# G-Cacher-Schematic_2026-07-06.net
KiCad netlist of a schematic drawn in Altium Designer
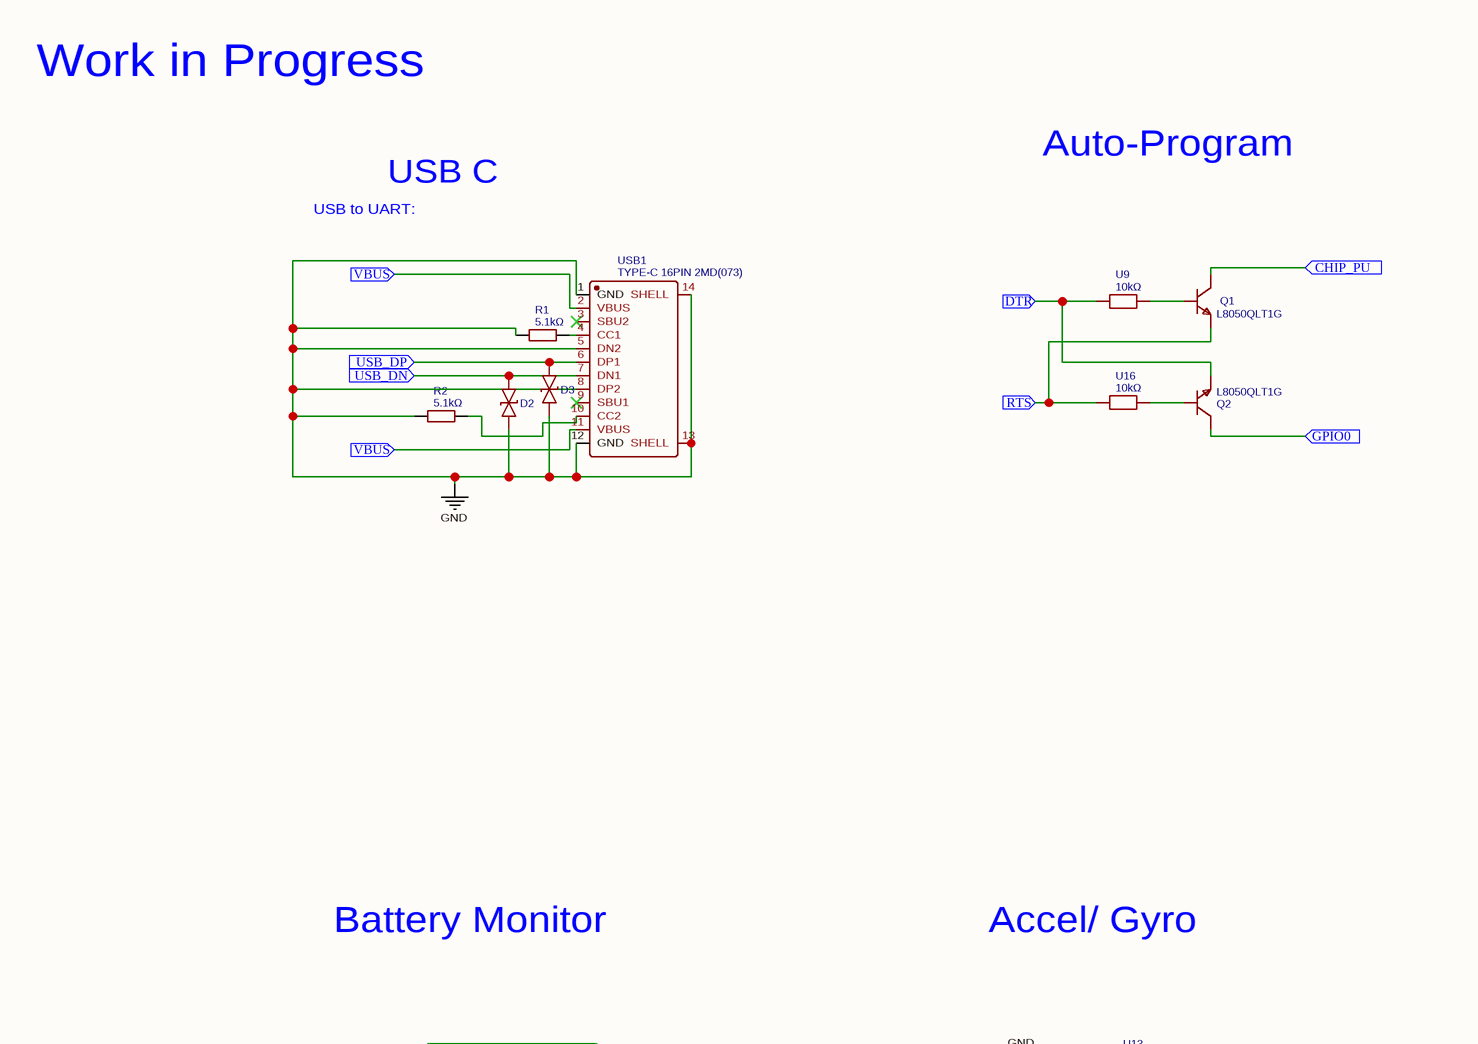
[diagram p0: G-Cacher-Schematic_2026-07-06.schdoc, top left]
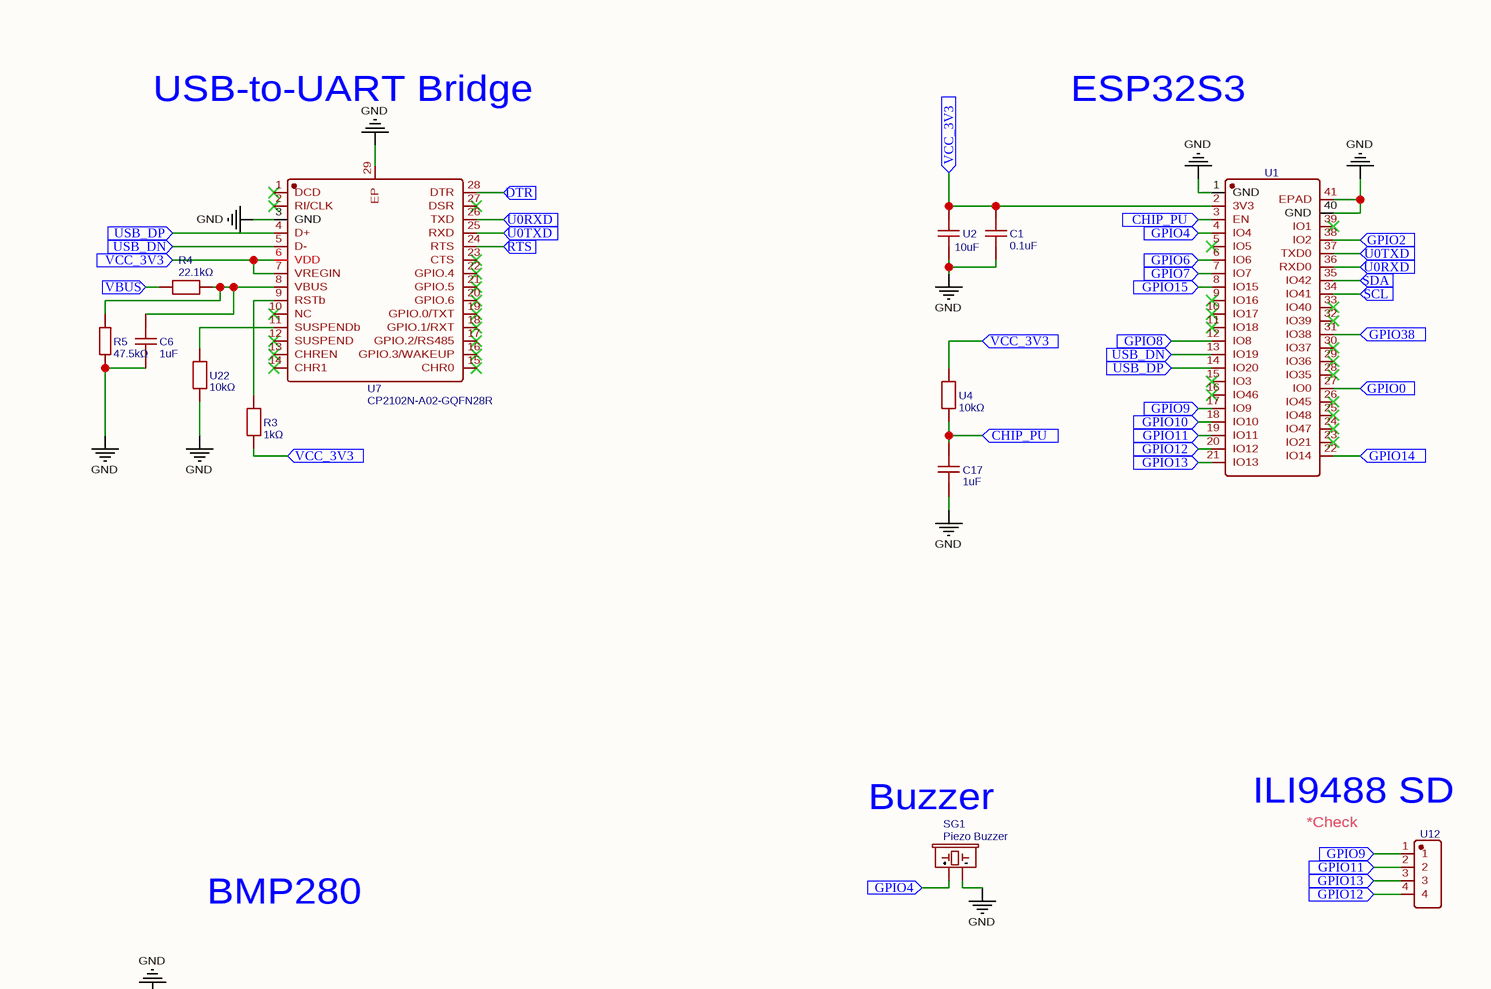
[diagram p1: G-Cacher-Schematic_2026-07-06.schdoc, top right]
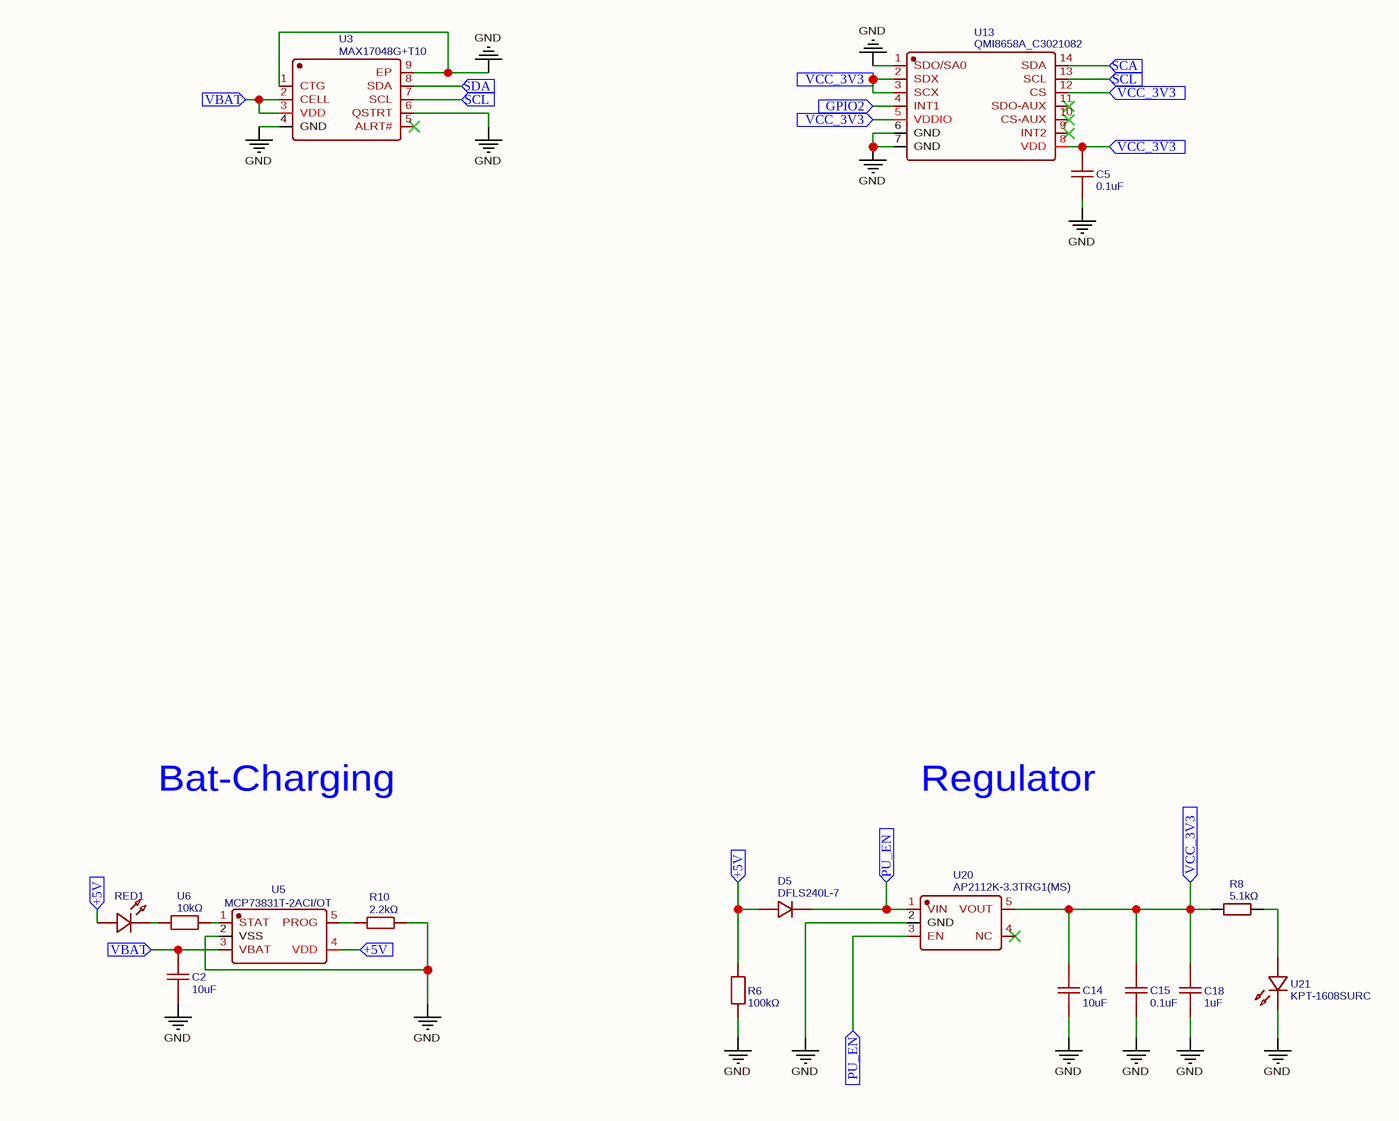
[diagram p2: G-Cacher-Schematic_2026-07-06.schdoc, bottom left]
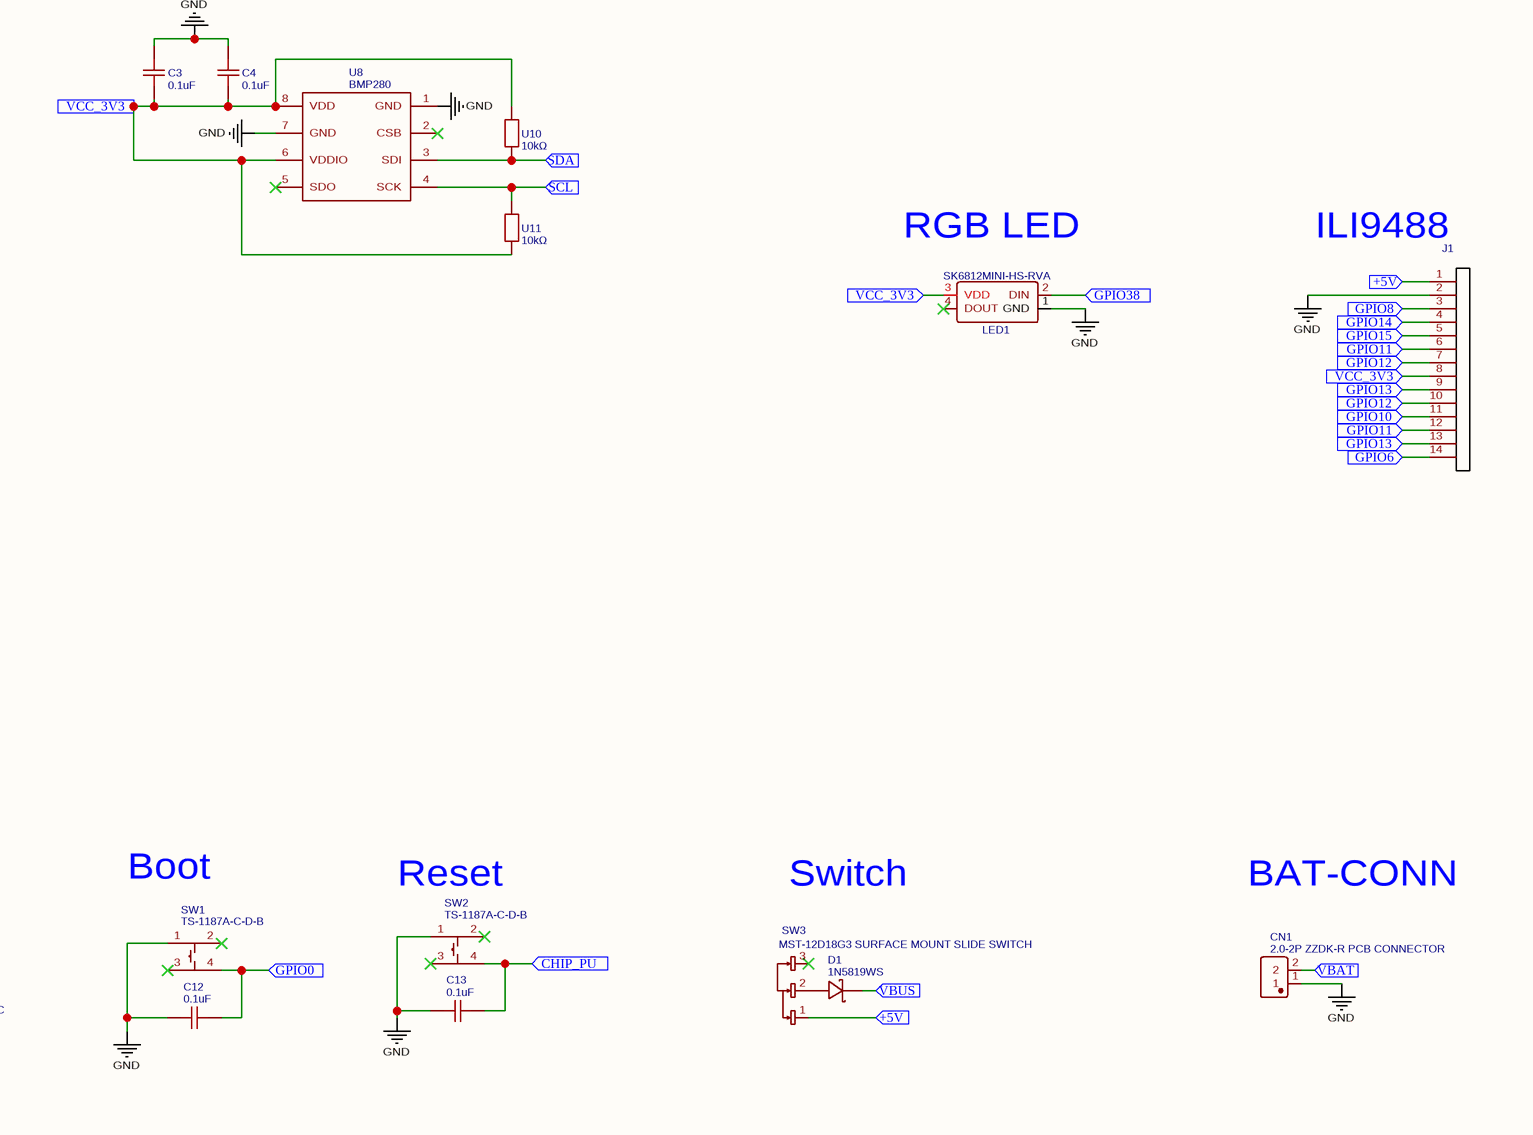
[diagram p3: G-Cacher-Schematic_2026-07-06.schdoc, bottom right]

(export (version "E")
  (design (tool "Eeschema 10.0.6"))
  (components
    (comp (ref "C1")
      (value "0.1uF")
      (fields
        (field (name "MANUFACTURER") "TDK")
        (field (name "MANUFACTURER PART") "C1005X5R1E104M050BC")
        (field (name "CONTRIBUTOR") "lcsc")
      )
      (libsource (lib "altium-import") (part "root_1_0.1uF_"))
    )
    (comp (ref "C2")
      (value "10uF")
      (fields (field (name "MANUFACTURER") "FH(风华)") (field (name "MANUFACTURER PART") "0603X106M100NT"))
      (libsource (lib "altium-import") (part "root_1_10uF_"))
    )
    (comp (ref "C3")
      (value "0.1uF")
      (fields
        (field (name "MANUFACTURER") "TDK")
        (field (name "MANUFACTURER PART") "C1005X5R1E104M050BC")
        (field (name "CONTRIBUTOR") "lcsc")
      )
      (libsource (lib "altium-import") (part "root_1_0.1uF_"))
    )
    (comp (ref "C4")
      (value "0.1uF")
      (fields
        (field (name "MANUFACTURER") "TDK")
        (field (name "MANUFACTURER PART") "C1005X5R1E104M050BC")
        (field (name "CONTRIBUTOR") "lcsc")
      )
      (libsource (lib "altium-import") (part "root_1_0.1uF_"))
    )
    (comp (ref "C5")
      (value "0.1uF")
      (fields
        (field (name "MANUFACTURER") "TDK")
        (field (name "MANUFACTURER PART") "C1005X5R1E104M050BC")
        (field (name "CONTRIBUTOR") "lcsc")
      )
      (libsource (lib "altium-import") (part "root_1_0.1uF_"))
    )
    (comp (ref "C6")
      (value "1uF")
      (fields
        (field (name "MANUFACTURER") "TDK")
        (field (name "MANUFACTURER PART") "YNA18B3U0G105MT000N")
        (field (name "CONTRIBUTOR") "lcsc")
      )
      (libsource (lib "altium-import") (part "root_1_1uF_"))
    )
    (comp (ref "C12")
      (value "0.1uF")
      (fields
        (field (name "MANUFACTURER") "TDK")
        (field (name "MANUFACTURER PART") "C1005X5R1E104M050BC")
        (field (name "CONTRIBUTOR") "lcsc")
      )
      (libsource (lib "altium-import") (part "root_2_0.1uF_"))
    )
    (comp (ref "C13")
      (value "0.1uF")
      (fields
        (field (name "MANUFACTURER") "TDK")
        (field (name "MANUFACTURER PART") "C1005X5R1E104M050BC")
        (field (name "CONTRIBUTOR") "lcsc")
      )
      (libsource (lib "altium-import") (part "root_2_0.1uF_"))
    )
    (comp (ref "C14")
      (value "10uF")
      (fields (field (name "MANUFACTURER") "FH(风华)") (field (name "MANUFACTURER PART") "0603X106M100NT"))
      (libsource (lib "altium-import") (part "root_1_10uF_"))
    )
    (comp (ref "C15")
      (value "0.1uF")
      (fields
        (field (name "MANUFACTURER") "TDK")
        (field (name "MANUFACTURER PART") "C1005X5R1E104M050BC")
        (field (name "CONTRIBUTOR") "lcsc")
      )
      (libsource (lib "altium-import") (part "root_1_0.1uF_"))
    )
    (comp (ref "C17")
      (value "1uF")
      (fields
        (field (name "MANUFACTURER") "TDK")
        (field (name "MANUFACTURER PART") "YNA18B3U0G105MT000N")
        (field (name "CONTRIBUTOR") "lcsc")
      )
      (libsource (lib "altium-import") (part "root_1_1uF_"))
    )
    (comp (ref "C18")
      (value "1uF")
      (fields
        (field (name "MANUFACTURER") "TDK")
        (field (name "MANUFACTURER PART") "YNA18B3U0G105MT000N")
        (field (name "CONTRIBUTOR") "lcsc")
      )
      (libsource (lib "altium-import") (part "root_1_1uF_"))
    )
    (comp (ref "CN1")
      (value "2.0-2P ZZDK-R PCB CONNECTOR")
      (fields
        (field (name "MANUFACTURER") "SHOU HAN(首韩)")
        (field (name "MANUFACTURER PART") "2.0-2P ZZDK-R PCB Connector")
        (field (name "CONTRIBUTOR") "lcsc")
      )
      (libsource (lib "altium-import") (part "root_2_2.0-2P ZZDK-R PCB CONNECTOR_"))
    )
    (comp (ref "D1")
      (value "1N5819WS")
      (fields (field (name "MANUFACTURER") "Hottech(合科泰)") (field (name "CONTRIBUTOR") "qarnet"))
      (libsource (lib "altium-import") (part "root_2_1N5819WS_"))
    )
    (comp (ref "D2")
      (value "LESD5D5.0CT1G")
      (fields (field (name "MANUFACTURER") "LRC(乐山无线电)") (field (name "CONTRIBUTOR") "LCSC"))
      (libsource (lib "altium-import") (part "root_3_LESD5D5.0CT1G_"))
    )
    (comp (ref "D3")
      (value "LESD5D5.0CT1G")
      (fields (field (name "MANUFACTURER") "LRC(乐山无线电)") (field (name "CONTRIBUTOR") "LCSC"))
      (libsource (lib "altium-import") (part "root_3_LESD5D5.0CT1G_"))
    )
    (comp (ref "D5")
      (value "DFLS240L-7")
      (fields (field (name "MANUFACTURER") "DIODES(美台)") (field (name "CONTRIBUTOR") "LCSC"))
      (libsource (lib "altium-import") (part "root_2_DFLS240L-7_"))
    )
    (comp (ref "J1")
      (value "14 PIN FEMALE HEADER")
      (fields (field (name "CONTRIBUTOR") "rnor"))
      (libsource (lib "altium-import") (part "root_0_14 PIN FEMALE HEADER_"))
    )
    (comp (ref "LED1")
      (value "SK6812MINI-HS-RVA")
      (fields (field (name "MANUFACTURER") "欧思科光电") (field (name "CONTRIBUTOR") "lcsc"))
      (libsource (lib "altium-import") (part "root_0_SK6812MINI-HS-RVA_"))
    )
    (comp (ref "Q1")
      (value "L8050QLT1G")
      (fields (field (name "MANUFACTURER") "LRC(乐山无线电)"))
      (libsource (lib "altium-import") (part "root_0_L8050QLT1G_"))
    )
    (comp (ref "Q2")
      (value "L8050QLT1G")
      (fields (field (name "MANUFACTURER") "LRC(乐山无线电)"))
      (libsource (lib "") (part "root_0_L8050QLT1G__1"))
    )
    (comp (ref "R1")
      (value "5.1kΩ")
      (fields
        (field (name "MANUFACTURER") "UNI-ROYAL(厚声)")
        (field (name "MANUFACTURER PART") "0402WGF5101TCE")
      )
      (libsource (lib "altium-import") (part "root_0_5.1kΩ_"))
    )
    (comp (ref "R2")
      (value "5.1kΩ")
      (fields
        (field (name "MANUFACTURER") "UNI-ROYAL(厚声)")
        (field (name "MANUFACTURER PART") "0402WGF5101TCE")
      )
      (libsource (lib "altium-import") (part "root_0_5.1kΩ_"))
    )
    (comp (ref "R3")
      (value "1kΩ")
      (fields
        (field (name "MANUFACTURER") "RESI(开步睿思)")
        (field (name "MANUFACTURER PART") "PTFR0603Q1K00N9")
        (field (name "CONTRIBUTOR") "lcsc")
      )
      (libsource (lib "altium-import") (part "root_1_1kΩ_"))
    )
    (comp (ref "R4")
      (value "22.1kΩ")
      (fields
        (field (name "MANUFACTURER") "FOJAN(富捷)")
        (field (name "MANUFACTURER PART") "FRC0402F2212TS")
        (field (name "CONTRIBUTOR") "lcsc")
      )
      (libsource (lib "altium-import") (part "root_0_22.1kΩ_"))
    )
    (comp (ref "R5")
      (value "47.5kΩ")
      (fields
        (field (name "MANUFACTURER") "FH(风华)")
        (field (name "MANUFACTURER PART") "RC-02K4752FT")
        (field (name "CONTRIBUTOR") "LCSC")
      )
      (libsource (lib "altium-import") (part "root_1_47.5kΩ_"))
    )
    (comp (ref "R6")
      (value "100kΩ")
      (fields
        (field (name "MANUFACTURER") "EVER OHMS(天二科技)")
        (field (name "MANUFACTURER PART") "TR0603B100KP0525Z")
        (field (name "CONTRIBUTOR") "lcsc")
      )
      (libsource (lib "altium-import") (part "root_1_100kΩ_"))
    )
    (comp (ref "R8")
      (value "5.1kΩ")
      (fields
        (field (name "MANUFACTURER") "UNI-ROYAL(厚声)")
        (field (name "MANUFACTURER PART") "0402WGF5101TCE")
      )
      (libsource (lib "altium-import") (part "root_0_5.1kΩ_"))
    )
    (comp (ref "R10")
      (value "2.2kΩ")
      (fields
        (field (name "MANUFACTURER") "Tyohm(幸亚电阻)")
        (field (name "MANUFACTURER PART") "RMC04022.2K5%N")
        (field (name "CONTRIBUTOR") "LCSC")
      )
      (libsource (lib "altium-import") (part "root_2_2.2kΩ_"))
    )
    (comp (ref "RED1")
      (value "F.0603.00008/P2-0603R1TS2-06T-002")
      (fields (field (name "MANUFACTURER") "TUOZHAN(拓展光电)") (field (name "CONTRIBUTOR") "lcsc"))
      (libsource (lib "altium-import") (part "root_0_F.0603.00008/P2-0603R1TS2-06T-002_"))
    )
    (comp (ref "SG1")
      (value "Piezo Buzzer")
      (fields (field (name "CONTRIBUTOR") "SparkFun"))
      (libsource (lib "altium-import") (part "root_0_Piezo Buzzer_"))
    )
    (comp (ref "SW1")
      (value "TS-1187A-C-D-B")
      (fields (field (name "MANUFACTURER") "XKB Connection(中国星坤)") (field (name "CONTRIBUTOR") "LCSC"))
      (libsource (lib "altium-import") (part "root_0_TS-1187A-C-D-B_"))
    )
    (comp (ref "SW2")
      (value "TS-1187A-C-D-B")
      (fields (field (name "MANUFACTURER") "XKB Connection(中国星坤)") (field (name "CONTRIBUTOR") "LCSC"))
      (libsource (lib "altium-import") (part "root_0_TS-1187A-C-D-B_"))
    )
    (comp (ref "SW3")
      (value "MST-12D18G3 SURFACE MOUNT SLIDE SWITCH")
      (fields
        (field (name "MANUFACTURER") "SHOU HAN(首韩)")
        (field (name "MANUFACTURER PART") "MST-12D18G3 Surface Mount Slide Switch")
        (field (name "CONTRIBUTOR") "lcsc")
      )
      (libsource (lib "altium-import") (part "root_1_MST-12D18G3 SURFACE MOUNT SLIDE SWITCH_"))
    )
    (comp (ref "U1")
      (value "ESPS3-32-WROOM-1-N16R8")
      (fields (field (name "CONTRIBUTOR") "lcsc"))
      (libsource (lib "altium-import") (part "root_0_ESPS3-32-WROOM-1-N16R8_"))
    )
    (comp (ref "U2")
      (value "10uF")
      (fields
        (field (name "MANUFACTURER") "Chinocera(华瓷)")
        (field (name "MANUFACTURER PART") "HGC0603R5106K250NTHJ")
        (field (name "CONTRIBUTOR") "lcsc")
      )
      (libsource (lib "altium-import") (part "root_1_10uF_"))
    )
    (comp (ref "U3")
      (value "MAX17048G+T10")
      (fields (field (name "MANUFACTURER") "ADI(亚德诺)/MAXIM(美信)") (field (name "CONTRIBUTOR") "LCSC"))
      (libsource (lib "altium-import") (part "root_0_MAX17048G+T10_"))
    )
    (comp (ref "U4")
      (value "10kΩ")
      (fields
        (field (name "MANUFACTURER") "FH(风华)")
        (field (name "MANUFACTURER PART") "THC02H1002BT")
        (field (name "CONTRIBUTOR") "lcsc")
      )
      (libsource (lib "altium-import") (part "root_1_10kΩ_"))
    )
    (comp (ref "U5")
      (value "MCP73831T-2ACI/OT")
      (fields (field (name "MANUFACTURER") "MICROCHIP(美国微芯)") (field (name "CONTRIBUTOR") "LCSC"))
      (libsource (lib "altium-import") (part "root_0_MCP73831T-2ACI/OT_"))
    )
    (comp (ref "U6")
      (value "10kΩ")
      (fields
        (field (name "MANUFACTURER") "TE Connectivity(泰科电子)")
        (field (name "MANUFACTURER PART") "CRGH0603F10K")
        (field (name "CONTRIBUTOR") "lcsc")
      )
      (libsource (lib "altium-import") (part "root_2_10kΩ_"))
    )
    (comp (ref "U7")
      (value "CP2102N-A02-GQFN28R")
      (fields (field (name "MANUFACTURER") "SKYWORKS/SILICON LABS(芯科)") (field (name "CONTRIBUTOR") "LCSC"))
      (libsource (lib "altium-import") (part "root_0_CP2102N-A02-GQFN28R_"))
    )
    (comp (ref "U8")
      (value "BMP280")
      (fields (field (name "MANUFACTURER") "Bosch(博世)"))
      (libsource (lib "altium-import") (part "root_0_BMP280_"))
    )
    (comp (ref "U9")
      (value "10kΩ")
      (fields
        (field (name "MANUFACTURER") "TE Connectivity(泰科电子)")
        (field (name "MANUFACTURER PART") "CRGH0603F10K")
        (field (name "CONTRIBUTOR") "lcsc")
      )
      (libsource (lib "altium-import") (part "root_0_10kΩ_"))
    )
    (comp (ref "U10")
      (value "10kΩ")
      (fields
        (field (name "MANUFACTURER") "TE Connectivity(泰科电子)")
        (field (name "MANUFACTURER PART") "CRGH0603F10K")
        (field (name "CONTRIBUTOR") "lcsc")
      )
      (libsource (lib "altium-import") (part "root_3_10kΩ_"))
    )
    (comp (ref "U11")
      (value "10kΩ")
      (fields
        (field (name "MANUFACTURER") "TE Connectivity(泰科电子)")
        (field (name "MANUFACTURER PART") "CRGH0603F10K")
        (field (name "CONTRIBUTOR") "lcsc")
      )
      (libsource (lib "altium-import") (part "root_1_10kΩ_"))
    )
    (comp (ref "U12")
      (value "SSW-104-01-T-S")
      (fields (field (name "MANUFACTURER") "SAMTEC") (field (name "CONTRIBUTOR") "lcsc"))
      (libsource (lib "altium-import") (part "root_0_SSW-104-01-T-S_"))
    )
    (comp (ref "U13")
      (value "QMI8658A_C3021082")
      (fields
        (field (name "MANUFACTURER") "QST(上海矽睿)")
        (field (name "MANUFACTURER PART") "QMI8658A")
        (field (name "CONTRIBUTOR") "lcsc")
      )
      (libsource (lib "altium-import") (part "root_0_QMI8658A_C3021082_"))
    )
    (comp (ref "U16")
      (value "10kΩ")
      (fields
        (field (name "MANUFACTURER") "TE Connectivity(泰科电子)")
        (field (name "MANUFACTURER PART") "CRGH0603F10K")
        (field (name "CONTRIBUTOR") "lcsc")
      )
      (libsource (lib "altium-import") (part "root_0_10kΩ_"))
    )
    (comp (ref "U20")
      (value "AP2112K-3.3TRG1(MS)")
      (fields (field (name "MANUFACTURER") "MSKSEMI(美森科)") (field (name "CONTRIBUTOR") "lcsc"))
      (libsource (lib "altium-import") (part "root_0_AP2112K-3.3TRG1(MS)_"))
    )
    (comp (ref "U21")
      (value "KPT-1608SURC")
      (fields (field (name "MANUFACTURER") "Kingbright") (field (name "CONTRIBUTOR") "lcsc"))
      (libsource (lib "altium-import") (part "root_1_KPT-1608SURC_"))
    )
    (comp (ref "U22")
      (value "10kΩ")
      (fields
        (field (name "MANUFACTURER") "TE Connectivity(泰科电子)")
        (field (name "MANUFACTURER PART") "CRGH0603F10K")
        (field (name "CONTRIBUTOR") "lcsc")
      )
      (libsource (lib "altium-import") (part "root_1_10kΩ_"))
    )
    (comp (ref "USB1")
      (value "TYPE-C 16PIN 2MD(073)")
      (fields (field (name "MANUFACTURER") "SHOU HAN(首韩)") (field (name "CONTRIBUTOR") "LCSC"))
      (libsource (lib "altium-import") (part "root_0_TYPE-C 16PIN 2MD(073)_"))
    )
  )
  (nets
    (net (code "1") (name "/+5V") (class "Default")
      (node (ref "D5") (pin "2") (pinfunction "2_2") (pintype "passive"))
      (node (ref "J1") (pin "1") (pinfunction "1_1") (pintype "passive"))
      (node (ref "R6") (pin "2") (pinfunction "2_2") (pintype "passive"))
      (node (ref "RED1") (pin "1") (pinfunction "+_1") (pintype "passive"))
      (node (ref "SW3") (pin "1") (pinfunction "1_1") (pintype "passive"))
      (node (ref "U5") (pin "4") (pinfunction "VDD_4") (pintype "passive"))
    )
    (net (code "2") (name "/CHIP_PU") (class "Default")
      (node (ref "C13") (pin "1") (pinfunction "1_1") (pintype "passive"))
      (node (ref "C17") (pin "2") (pinfunction "2_2") (pintype "passive"))
      (node (ref "Q1") (pin "3") (pinfunction "C_3") (pintype "passive"))
      (node (ref "SW2") (pin "4") (pinfunction "D_4") (pintype "passive"))
      (node (ref "U1") (pin "3") (pinfunction "EN_3") (pintype "passive"))
      (node (ref "U4") (pin "1") (pinfunction "1_1") (pintype "passive"))
    )
    (net (code "3") (name "/DTR") (class "Default")
      (node (ref "Q2") (pin "2") (pinfunction "E_2") (pintype "passive"))
      (node (ref "U7") (pin "28") (pinfunction "DTR_28") (pintype "passive"))
      (node (ref "U9") (pin "1") (pinfunction "1_1") (pintype "passive"))
    )
    (net (code "4") (name "/GPIO0") (class "Default")
      (node (ref "C12") (pin "1") (pinfunction "1_1") (pintype "passive"))
      (node (ref "Q2") (pin "3") (pinfunction "C_3") (pintype "passive"))
      (node (ref "SW1") (pin "4") (pinfunction "D_4") (pintype "passive"))
      (node (ref "U1") (pin "27") (pinfunction "IO0_27") (pintype "passive"))
    )
    (net (code "5") (name "/GPIO2") (class "Default")
      (node (ref "U1") (pin "38") (pinfunction "IO2_38") (pintype "passive"))
      (node (ref "U13") (pin "4") (pinfunction "INT1_4") (pintype "passive"))
    )
    (net (code "6") (name "/GPIO4") (class "Default")
      (node (ref "SG1") (pin "+") (pinfunction "1_+") (pintype "passive"))
      (node (ref "U1") (pin "4") (pinfunction "IO4_4") (pintype "passive"))
    )
    (net (code "7") (name "/GPIO6") (class "Default")
      (node (ref "J1") (pin "14") (pinfunction "14_14") (pintype "passive"))
      (node (ref "U1") (pin "6") (pinfunction "IO6_6") (pintype "passive"))
    )
    (net (code "8") (name "/GPIO7") (class "Default")
      (node (ref "U1") (pin "7") (pinfunction "IO7_7") (pintype "passive"))
    )
    (net (code "9") (name "/GPIO8") (class "Default")
      (node (ref "J1") (pin "3") (pinfunction "3_3") (pintype "passive"))
      (node (ref "U1") (pin "12") (pinfunction "IO8_12") (pintype "passive"))
    )
    (net (code "10") (name "/GPIO9") (class "Default")
      (node (ref "U1") (pin "17") (pinfunction "IO9_17") (pintype "passive"))
      (node (ref "U12") (pin "1") (pinfunction "1_1") (pintype "passive"))
    )
    (net (code "11") (name "/GPIO10") (class "Default")
      (node (ref "J1") (pin "11") (pinfunction "11_11") (pintype "passive"))
      (node (ref "U1") (pin "18") (pinfunction "IO10_18") (pintype "passive"))
    )
    (net (code "12") (name "/GPIO11") (class "Default")
      (node (ref "J1") (pin "12") (pinfunction "12_12") (pintype "passive"))
      (node (ref "J1") (pin "6") (pinfunction "6_6") (pintype "passive"))
      (node (ref "U1") (pin "19") (pinfunction "IO11_19") (pintype "passive"))
      (node (ref "U12") (pin "2") (pinfunction "2_2") (pintype "passive"))
    )
    (net (code "13") (name "/GPIO12") (class "Default")
      (node (ref "J1") (pin "10") (pinfunction "10_10") (pintype "passive"))
      (node (ref "J1") (pin "7") (pinfunction "7_7") (pintype "passive"))
      (node (ref "U1") (pin "20") (pinfunction "IO12_20") (pintype "passive"))
      (node (ref "U12") (pin "4") (pinfunction "4_4") (pintype "passive"))
    )
    (net (code "14") (name "/GPIO13") (class "Default")
      (node (ref "J1") (pin "13") (pinfunction "13_13") (pintype "passive"))
      (node (ref "J1") (pin "9") (pinfunction "9_9") (pintype "passive"))
      (node (ref "U1") (pin "21") (pinfunction "IO13_21") (pintype "passive"))
      (node (ref "U12") (pin "3") (pinfunction "3_3") (pintype "passive"))
    )
    (net (code "15") (name "/GPIO14") (class "Default")
      (node (ref "J1") (pin "4") (pinfunction "4_4") (pintype "passive"))
      (node (ref "U1") (pin "22") (pinfunction "IO14_22") (pintype "passive"))
    )
    (net (code "16") (name "/GPIO15") (class "Default")
      (node (ref "J1") (pin "5") (pinfunction "5_5") (pintype "passive"))
      (node (ref "U1") (pin "8") (pinfunction "IO15_8") (pintype "passive"))
    )
    (net (code "17") (name "/GPIO38") (class "Default")
      (node (ref "LED1") (pin "2") (pinfunction "DIN_2") (pintype "passive"))
      (node (ref "U1") (pin "31") (pinfunction "IO38_31") (pintype "passive"))
    )
    (net (code "18") (name "/PU_EN") (class "Default")
      (node (ref "D5") (pin "1") (pinfunction "1_1") (pintype "passive"))
      (node (ref "U20") (pin "1") (pinfunction "VIN_1") (pintype "passive"))
      (node (ref "U20") (pin "3") (pinfunction "EN_3") (pintype "passive"))
    )
    (net (code "19") (name "/RTS") (class "Default")
      (node (ref "Q1") (pin "2") (pinfunction "E_2") (pintype "passive"))
      (node (ref "U16") (pin "1") (pinfunction "1_1") (pintype "passive"))
      (node (ref "U7") (pin "24") (pinfunction "RTS_24") (pintype "passive"))
    )
    (net (code "20") (name "/SCA") (class "Default")
      (node (ref "U13") (pin "14") (pinfunction "SDA_14") (pintype "passive"))
    )
    (net (code "21") (name "/SCL") (class "Default")
      (node (ref "U1") (pin "34") (pinfunction "IO41_34") (pintype "passive"))
      (node (ref "U11") (pin "2") (pinfunction "2_2") (pintype "passive"))
      (node (ref "U13") (pin "13") (pinfunction "SCL_13") (pintype "passive"))
      (node (ref "U3") (pin "7") (pinfunction "SCL_7") (pintype "passive"))
      (node (ref "U8") (pin "4") (pinfunction "SCK_4") (pintype "passive"))
    )
    (net (code "22") (name "/SDA") (class "Default")
      (node (ref "U1") (pin "35") (pinfunction "IO42_35") (pintype "passive"))
      (node (ref "U10") (pin "2") (pinfunction "2_2") (pintype "passive"))
      (node (ref "U3") (pin "8") (pinfunction "SDA_8") (pintype "passive"))
      (node (ref "U8") (pin "3") (pinfunction "SDI_3") (pintype "passive"))
    )
    (net (code "23") (name "/U0RXD") (class "Default")
      (node (ref "U1") (pin "36") (pinfunction "RXD0_36") (pintype "passive"))
      (node (ref "U7") (pin "26") (pinfunction "TXD_26") (pintype "passive"))
    )
    (net (code "24") (name "/U0TXD") (class "Default")
      (node (ref "U1") (pin "37") (pinfunction "TXD0_37") (pintype "passive"))
      (node (ref "U7") (pin "25") (pinfunction "RXD_25") (pintype "passive"))
    )
    (net (code "25") (name "/USB_DN") (class "Default")
      (node (ref "D2") (pin "1") (pinfunction "1_1") (pintype "passive"))
      (node (ref "U1") (pin "13") (pinfunction "IO19_13") (pintype "passive"))
      (node (ref "U7") (pin "5") (pinfunction "D-_5") (pintype "passive"))
      (node (ref "USB1") (pin "7") (pinfunction "DN1_7") (pintype "passive"))
    )
    (net (code "26") (name "/USB_DP") (class "Default")
      (node (ref "D3") (pin "1") (pinfunction "1_1") (pintype "passive"))
      (node (ref "U1") (pin "14") (pinfunction "IO20_14") (pintype "passive"))
      (node (ref "U7") (pin "4") (pinfunction "D+_4") (pintype "passive"))
      (node (ref "USB1") (pin "6") (pinfunction "DP1_6") (pintype "passive"))
    )
    (net (code "27") (name "/VBAT") (class "Default")
      (node (ref "C2") (pin "2") (pinfunction "2_2") (pintype "passive"))
      (node (ref "CN1") (pin "2") (pinfunction "2_2") (pintype "passive"))
      (node (ref "U3") (pin "2") (pinfunction "CELL_2") (pintype "passive"))
      (node (ref "U3") (pin "3") (pinfunction "VDD_3") (pintype "passive"))
      (node (ref "U5") (pin "3") (pinfunction "VBAT_3") (pintype "passive"))
    )
    (net (code "28") (name "/VBUS") (class "Default")
      (node (ref "D1") (pin "1") (pinfunction "K_1") (pintype "passive"))
      (node (ref "R4") (pin "1") (pinfunction "1_1") (pintype "passive"))
      (node (ref "USB1") (pin "11") (pinfunction "VBUS_11") (pintype "passive"))
      (node (ref "USB1") (pin "2") (pinfunction "VBUS_2") (pintype "passive"))
    )
    (net (code "29") (name "/VCC_3V3") (class "Default")
      (node (ref "C1") (pin "2") (pinfunction "2_2") (pintype "passive"))
      (node (ref "C14") (pin "2") (pinfunction "2_2") (pintype "passive"))
      (node (ref "C15") (pin "2") (pinfunction "2_2") (pintype "passive"))
      (node (ref "C18") (pin "2") (pinfunction "2_2") (pintype "passive"))
      (node (ref "C3") (pin "1") (pinfunction "1_1") (pintype "passive"))
      (node (ref "C4") (pin "1") (pinfunction "1_1") (pintype "passive"))
      (node (ref "C5") (pin "2") (pinfunction "2_2") (pintype "passive"))
      (node (ref "J1") (pin "8") (pinfunction "8_8") (pintype "passive"))
      (node (ref "LED1") (pin "3") (pinfunction "VDD_3") (pintype "passive"))
      (node (ref "R3") (pin "1") (pinfunction "1_1") (pintype "passive"))
      (node (ref "R8") (pin "1") (pinfunction "1_1") (pintype "passive"))
      (node (ref "U1") (pin "2") (pinfunction "3V3_2") (pintype "passive"))
      (node (ref "U10") (pin "1") (pinfunction "1_1") (pintype "passive"))
      (node (ref "U11") (pin "1") (pinfunction "1_1") (pintype "passive"))
      (node (ref "U13") (pin "12") (pinfunction "CS_12") (pintype "passive"))
      (node (ref "U13") (pin "2") (pinfunction "SDX_2") (pintype "passive"))
      (node (ref "U13") (pin "3") (pinfunction "SCX_3") (pintype "passive"))
      (node (ref "U13") (pin "5") (pinfunction "VDDIO_5") (pintype "passive"))
      (node (ref "U13") (pin "8") (pinfunction "VDD_8") (pintype "passive"))
      (node (ref "U2") (pin "2") (pinfunction "2_2") (pintype "passive"))
      (node (ref "U20") (pin "5") (pinfunction "VOUT_5") (pintype "passive"))
      (node (ref "U4") (pin "2") (pinfunction "2_2") (pintype "passive"))
      (node (ref "U7") (pin "6") (pinfunction "VDD_6") (pintype "passive"))
      (node (ref "U7") (pin "7") (pinfunction "VREGIN_7") (pintype "passive"))
      (node (ref "U8") (pin "6") (pinfunction "VDDIO_6") (pintype "passive"))
      (node (ref "U8") (pin "8") (pinfunction "VDD_8") (pintype "passive"))
    )
    (net (code "30") (name "GND") (class "Default")
      (node (ref "C1") (pin "1") (pinfunction "1_1") (pintype "passive"))
      (node (ref "C12") (pin "2") (pinfunction "2_2") (pintype "passive"))
      (node (ref "C13") (pin "2") (pinfunction "2_2") (pintype "passive"))
      (node (ref "C14") (pin "1") (pinfunction "1_1") (pintype "passive"))
      (node (ref "C15") (pin "1") (pinfunction "1_1") (pintype "passive"))
      (node (ref "C17") (pin "1") (pinfunction "1_1") (pintype "passive"))
      (node (ref "C18") (pin "1") (pinfunction "1_1") (pintype "passive"))
      (node (ref "C2") (pin "1") (pinfunction "1_1") (pintype "passive"))
      (node (ref "C3") (pin "2") (pinfunction "2_2") (pintype "passive"))
      (node (ref "C4") (pin "2") (pinfunction "2_2") (pintype "passive"))
      (node (ref "C5") (pin "1") (pinfunction "1_1") (pintype "passive"))
      (node (ref "C6") (pin "1") (pinfunction "1_1") (pintype "passive"))
      (node (ref "CN1") (pin "1") (pinfunction "1_1") (pintype "passive"))
      (node (ref "D2") (pin "2") (pinfunction "2_2") (pintype "passive"))
      (node (ref "D3") (pin "2") (pinfunction "2_2") (pintype "passive"))
      (node (ref "J1") (pin "2") (pinfunction "2_2") (pintype "passive"))
      (node (ref "LED1") (pin "1") (pinfunction "GND_1") (pintype "passive"))
      (node (ref "R1") (pin "1") (pinfunction "1_1") (pintype "passive"))
      (node (ref "R10") (pin "1") (pinfunction "1_1") (pintype "passive"))
      (node (ref "R2") (pin "1") (pinfunction "1_1") (pintype "passive"))
      (node (ref "R5") (pin "1") (pinfunction "1_1") (pintype "passive"))
      (node (ref "R6") (pin "1") (pinfunction "1_1") (pintype "passive"))
      (node (ref "SG1") (pin "-") (pinfunction "2_-") (pintype "passive"))
      (node (ref "SW1") (pin "1") (pinfunction "A_1") (pintype "passive"))
      (node (ref "SW2") (pin "1") (pinfunction "A_1") (pintype "passive"))
      (node (ref "U1") (pin "1") (pinfunction "GND_1") (pintype "passive"))
      (node (ref "U1") (pin "40") (pinfunction "GND_40") (pintype "passive"))
      (node (ref "U1") (pin "41") (pinfunction "EPAD_41") (pintype "passive"))
      (node (ref "U13") (pin "1") (pinfunction "SDO/SA0_1") (pintype "passive"))
      (node (ref "U13") (pin "6") (pinfunction "GND_6") (pintype "passive"))
      (node (ref "U13") (pin "7") (pinfunction "GND_7") (pintype "passive"))
      (node (ref "U2") (pin "1") (pinfunction "1_1") (pintype "passive"))
      (node (ref "U20") (pin "2") (pinfunction "GND_2") (pintype "passive"))
      (node (ref "U21") (pin "1") (pinfunction "K_1") (pintype "passive"))
      (node (ref "U22") (pin "1") (pinfunction "1_1") (pintype "passive"))
      (node (ref "U3") (pin "1") (pinfunction "CTG_1") (pintype "passive"))
      (node (ref "U3") (pin "4") (pinfunction "GND_4") (pintype "passive"))
      (node (ref "U3") (pin "6") (pinfunction "QSTRT_6") (pintype "passive"))
      (node (ref "U3") (pin "9") (pinfunction "EP_9") (pintype "passive"))
      (node (ref "U5") (pin "2") (pinfunction "VSS_2") (pintype "passive"))
      (node (ref "U7") (pin "29") (pinfunction "EP_29") (pintype "passive"))
      (node (ref "U7") (pin "3") (pinfunction "GND_3") (pintype "passive"))
      (node (ref "U8") (pin "1") (pinfunction "GND_1") (pintype "passive"))
      (node (ref "U8") (pin "7") (pinfunction "GND_7") (pintype "passive"))
      (node (ref "USB1") (pin "1") (pinfunction "GND_1") (pintype "passive"))
      (node (ref "USB1") (pin "12") (pinfunction "GND_12") (pintype "passive"))
      (node (ref "USB1") (pin "13") (pinfunction "SHELL_13") (pintype "passive"))
      (node (ref "USB1") (pin "14") (pinfunction "SHELL_14") (pintype "passive"))
      (node (ref "USB1") (pin "5") (pinfunction "DN2_5") (pintype "passive"))
      (node (ref "USB1") (pin "8") (pinfunction "DP2_8") (pintype "passive"))
    )
    (net (code "31") (name "Net-(D1-A)") (class "Default")
      (node (ref "D1") (pin "2") (pinfunction "A_2") (pintype "passive"))
      (node (ref "SW3") (pin "2") (pinfunction "2_2") (pintype "passive"))
    )
    (net (code "32") (name "Net-(Q1-B)") (class "Default")
      (node (ref "Q1") (pin "1") (pinfunction "B_1") (pintype "passive"))
      (node (ref "U9") (pin "2") (pinfunction "2_2") (pintype "passive"))
    )
    (net (code "33") (name "Net-(Q2-B)") (class "Default")
      (node (ref "Q2") (pin "1") (pinfunction "B_1") (pintype "passive"))
      (node (ref "U16") (pin "2") (pinfunction "2_2") (pintype "passive"))
    )
    (net (code "34") (name "Net-(RED1--)") (class "Default")
      (node (ref "RED1") (pin "2") (pinfunction "-_2") (pintype "passive"))
      (node (ref "U6") (pin "2") (pinfunction "2_2") (pintype "passive"))
    )
    (net (code "35") (name "Net-(U5-PROG)") (class "Default")
      (node (ref "R10") (pin "2") (pinfunction "2_2") (pintype "passive"))
      (node (ref "U5") (pin "5") (pinfunction "PROG_5") (pintype "passive"))
    )
    (net (code "36") (name "Net-(U5-STAT)") (class "Default")
      (node (ref "U5") (pin "1") (pinfunction "STAT_1") (pintype "passive"))
      (node (ref "U6") (pin "1") (pinfunction "1_1") (pintype "passive"))
    )
    (net (code "37") (name "Net-(U7-RSTb)") (class "Default")
      (node (ref "R3") (pin "2") (pinfunction "2_2") (pintype "passive"))
      (node (ref "U7") (pin "9") (pinfunction "RSTb_9") (pintype "passive"))
    )
    (net (code "38") (name "Net-(U7-SUSPENDb)") (class "Default")
      (node (ref "U22") (pin "2") (pinfunction "2_2") (pintype "passive"))
      (node (ref "U7") (pin "11") (pinfunction "SUSPENDb_11") (pintype "passive"))
    )
    (net (code "39") (name "Net-(U7-VBUS)") (class "Default")
      (node (ref "C6") (pin "2") (pinfunction "2_2") (pintype "passive"))
      (node (ref "R4") (pin "2") (pinfunction "2_2") (pintype "passive"))
      (node (ref "R5") (pin "2") (pinfunction "2_2") (pintype "passive"))
      (node (ref "U7") (pin "8") (pinfunction "VBUS_8") (pintype "passive"))
    )
    (net (code "40") (name "Net-(U21-A)") (class "Default")
      (node (ref "R8") (pin "2") (pinfunction "2_2") (pintype "passive"))
      (node (ref "U21") (pin "2") (pinfunction "A_2") (pintype "passive"))
    )
    (net (code "41") (name "Net-(USB1-CC1)") (class "Default")
      (node (ref "R1") (pin "2") (pinfunction "2_2") (pintype "passive"))
      (node (ref "USB1") (pin "4") (pinfunction "CC1_4") (pintype "passive"))
    )
    (net (code "42") (name "Net-(USB1-CC2)") (class "Default")
      (node (ref "R2") (pin "2") (pinfunction "2_2") (pintype "passive"))
      (node (ref "USB1") (pin "10") (pinfunction "CC2_10") (pintype "passive"))
    )
    (net (code "43") (name "unconnected-(LED1-DOUT-Pad4)") (class "Default")
      (node (ref "LED1") (pin "4") (pinfunction "DOUT_4") (pintype "passive+no_connect"))
    )
    (net (code "44") (name "unconnected-(SW1-B-Pad2)") (class "Default")
      (node (ref "SW1") (pin "2") (pinfunction "B_2") (pintype "passive+no_connect"))
    )
    (net (code "45") (name "unconnected-(SW1-C-Pad3)") (class "Default")
      (node (ref "SW1") (pin "3") (pinfunction "C_3") (pintype "passive+no_connect"))
    )
    (net (code "46") (name "unconnected-(SW2-B-Pad2)") (class "Default")
      (node (ref "SW2") (pin "2") (pinfunction "B_2") (pintype "passive+no_connect"))
    )
    (net (code "47") (name "unconnected-(SW2-C-Pad3)") (class "Default")
      (node (ref "SW2") (pin "3") (pinfunction "C_3") (pintype "passive+no_connect"))
    )
    (net (code "48") (name "unconnected-(SW3-Pad3)") (class "Default")
      (node (ref "SW3") (pin "3") (pinfunction "3_3") (pintype "passive+no_connect"))
    )
    (net (code "49") (name "unconnected-(U1-IO1-Pad39)") (class "Default")
      (node (ref "U1") (pin "39") (pinfunction "IO1_39") (pintype "passive+no_connect"))
    )
    (net (code "50") (name "unconnected-(U1-IO3-Pad15)") (class "Default")
      (node (ref "U1") (pin "15") (pinfunction "IO3_15") (pintype "passive+no_connect"))
    )
    (net (code "51") (name "unconnected-(U1-IO5-Pad5)") (class "Default")
      (node (ref "U1") (pin "5") (pinfunction "IO5_5") (pintype "passive+no_connect"))
    )
    (net (code "52") (name "unconnected-(U1-IO16-Pad9)") (class "Default")
      (node (ref "U1") (pin "9") (pinfunction "IO16_9") (pintype "passive+no_connect"))
    )
    (net (code "53") (name "unconnected-(U1-IO17-Pad10)") (class "Default")
      (node (ref "U1") (pin "10") (pinfunction "IO17_10") (pintype "passive+no_connect"))
    )
    (net (code "54") (name "unconnected-(U1-IO18-Pad11)") (class "Default")
      (node (ref "U1") (pin "11") (pinfunction "IO18_11") (pintype "passive+no_connect"))
    )
    (net (code "55") (name "unconnected-(U1-IO21-Pad23)") (class "Default")
      (node (ref "U1") (pin "23") (pinfunction "IO21_23") (pintype "passive+no_connect"))
    )
    (net (code "56") (name "unconnected-(U1-IO35-Pad28)") (class "Default")
      (node (ref "U1") (pin "28") (pinfunction "IO35_28") (pintype "passive+no_connect"))
    )
    (net (code "57") (name "unconnected-(U1-IO36-Pad29)") (class "Default")
      (node (ref "U1") (pin "29") (pinfunction "IO36_29") (pintype "passive+no_connect"))
    )
    (net (code "58") (name "unconnected-(U1-IO37-Pad30)") (class "Default")
      (node (ref "U1") (pin "30") (pinfunction "IO37_30") (pintype "passive+no_connect"))
    )
    (net (code "59") (name "unconnected-(U1-IO39-Pad32)") (class "Default")
      (node (ref "U1") (pin "32") (pinfunction "IO39_32") (pintype "passive+no_connect"))
    )
    (net (code "60") (name "unconnected-(U1-IO40-Pad33)") (class "Default")
      (node (ref "U1") (pin "33") (pinfunction "IO40_33") (pintype "passive+no_connect"))
    )
    (net (code "61") (name "unconnected-(U1-IO45-Pad26)") (class "Default")
      (node (ref "U1") (pin "26") (pinfunction "IO45_26") (pintype "passive+no_connect"))
    )
    (net (code "62") (name "unconnected-(U1-IO46-Pad16)") (class "Default")
      (node (ref "U1") (pin "16") (pinfunction "IO46_16") (pintype "passive+no_connect"))
    )
    (net (code "63") (name "unconnected-(U1-IO47-Pad24)") (class "Default")
      (node (ref "U1") (pin "24") (pinfunction "IO47_24") (pintype "passive+no_connect"))
    )
    (net (code "64") (name "unconnected-(U1-IO48-Pad25)") (class "Default")
      (node (ref "U1") (pin "25") (pinfunction "IO48_25") (pintype "passive+no_connect"))
    )
    (net (code "65") (name "unconnected-(U3-ALRT#-Pad5)") (class "Default")
      (node (ref "U3") (pin "5") (pinfunction "ALRT#_5") (pintype "passive+no_connect"))
    )
    (net (code "66") (name "unconnected-(U7-CHR0-Pad15)") (class "Default")
      (node (ref "U7") (pin "15") (pinfunction "CHR0_15") (pintype "passive+no_connect"))
    )
    (net (code "67") (name "unconnected-(U7-CHR1-Pad14)") (class "Default")
      (node (ref "U7") (pin "14") (pinfunction "CHR1_14") (pintype "passive+no_connect"))
    )
    (net (code "68") (name "unconnected-(U7-CHREN-Pad13)") (class "Default")
      (node (ref "U7") (pin "13") (pinfunction "CHREN_13") (pintype "passive+no_connect"))
    )
    (net (code "69") (name "unconnected-(U7-CTS-Pad23)") (class "Default")
      (node (ref "U7") (pin "23") (pinfunction "CTS_23") (pintype "passive+no_connect"))
    )
    (net (code "70") (name "unconnected-(U7-DCD-Pad1)") (class "Default")
      (node (ref "U7") (pin "1") (pinfunction "DCD_1") (pintype "passive+no_connect"))
    )
    (net (code "71") (name "unconnected-(U7-DSR-Pad27)") (class "Default")
      (node (ref "U7") (pin "27") (pinfunction "DSR_27") (pintype "passive+no_connect"))
    )
    (net (code "72") (name "unconnected-(U7-GPIO.0{slash}TXT-Pad19)") (class "Default")
      (node (ref "U7") (pin "19") (pinfunction "GPIO.0/TXT_19") (pintype "passive+no_connect"))
    )
    (net (code "73") (name "unconnected-(U7-GPIO.1{slash}RXT-Pad18)") (class "Default")
      (node (ref "U7") (pin "18") (pinfunction "GPIO.1/RXT_18") (pintype "passive+no_connect"))
    )
    (net (code "74") (name "unconnected-(U7-GPIO.2{slash}RS485-Pad17)") (class "Default")
      (node (ref "U7") (pin "17") (pinfunction "GPIO.2/RS485_17") (pintype "passive+no_connect"))
    )
    (net (code "75") (name "unconnected-(U7-GPIO.3{slash}WAKEUP-Pad16)") (class "Default")
      (node (ref "U7") (pin "16") (pinfunction "GPIO.3/WAKEUP_16") (pintype "passive+no_connect"))
    )
    (net (code "76") (name "unconnected-(U7-GPIO.4-Pad22)") (class "Default")
      (node (ref "U7") (pin "22") (pinfunction "GPIO.4_22") (pintype "passive+no_connect"))
    )
    (net (code "77") (name "unconnected-(U7-GPIO.5-Pad21)") (class "Default")
      (node (ref "U7") (pin "21") (pinfunction "GPIO.5_21") (pintype "passive+no_connect"))
    )
    (net (code "78") (name "unconnected-(U7-GPIO.6-Pad20)") (class "Default")
      (node (ref "U7") (pin "20") (pinfunction "GPIO.6_20") (pintype "passive+no_connect"))
    )
    (net (code "79") (name "unconnected-(U7-NC-Pad10)") (class "Default")
      (node (ref "U7") (pin "10") (pinfunction "NC_10") (pintype "passive+no_connect"))
    )
    (net (code "80") (name "unconnected-(U7-RI{slash}CLK-Pad2)") (class "Default")
      (node (ref "U7") (pin "2") (pinfunction "RI/CLK_2") (pintype "passive+no_connect"))
    )
    (net (code "81") (name "unconnected-(U7-SUSPEND-Pad12)") (class "Default")
      (node (ref "U7") (pin "12") (pinfunction "SUSPEND_12") (pintype "passive+no_connect"))
    )
    (net (code "82") (name "unconnected-(U8-CSB-Pad2)") (class "Default")
      (node (ref "U8") (pin "2") (pinfunction "CSB_2") (pintype "passive+no_connect"))
    )
    (net (code "83") (name "unconnected-(U8-SDO-Pad5)") (class "Default")
      (node (ref "U8") (pin "5") (pinfunction "SDO_5") (pintype "passive+no_connect"))
    )
    (net (code "84") (name "unconnected-(U13-CS-AUX-Pad10)") (class "Default")
      (node (ref "U13") (pin "10") (pinfunction "CS-AUX_10") (pintype "passive+no_connect"))
    )
    (net (code "85") (name "unconnected-(U13-INT2-Pad9)") (class "Default")
      (node (ref "U13") (pin "9") (pinfunction "INT2_9") (pintype "passive+no_connect"))
    )
    (net (code "86") (name "unconnected-(U13-SDO-AUX-Pad11)") (class "Default")
      (node (ref "U13") (pin "11") (pinfunction "SDO-AUX_11") (pintype "passive+no_connect"))
    )
    (net (code "87") (name "unconnected-(U20-NC-Pad4)") (class "Default")
      (node (ref "U20") (pin "4") (pinfunction "NC_4") (pintype "passive+no_connect"))
    )
    (net (code "88") (name "unconnected-(USB1-SBU1-Pad9)") (class "Default")
      (node (ref "USB1") (pin "9") (pinfunction "SBU1_9") (pintype "passive+no_connect"))
    )
    (net (code "89") (name "unconnected-(USB1-SBU2-Pad3)") (class "Default")
      (node (ref "USB1") (pin "3") (pinfunction "SBU2_3") (pintype "passive+no_connect"))
    )
  )
)
